# de0-nano_RMII.net
KiCad netlist of a schematic drawn in EAGLE
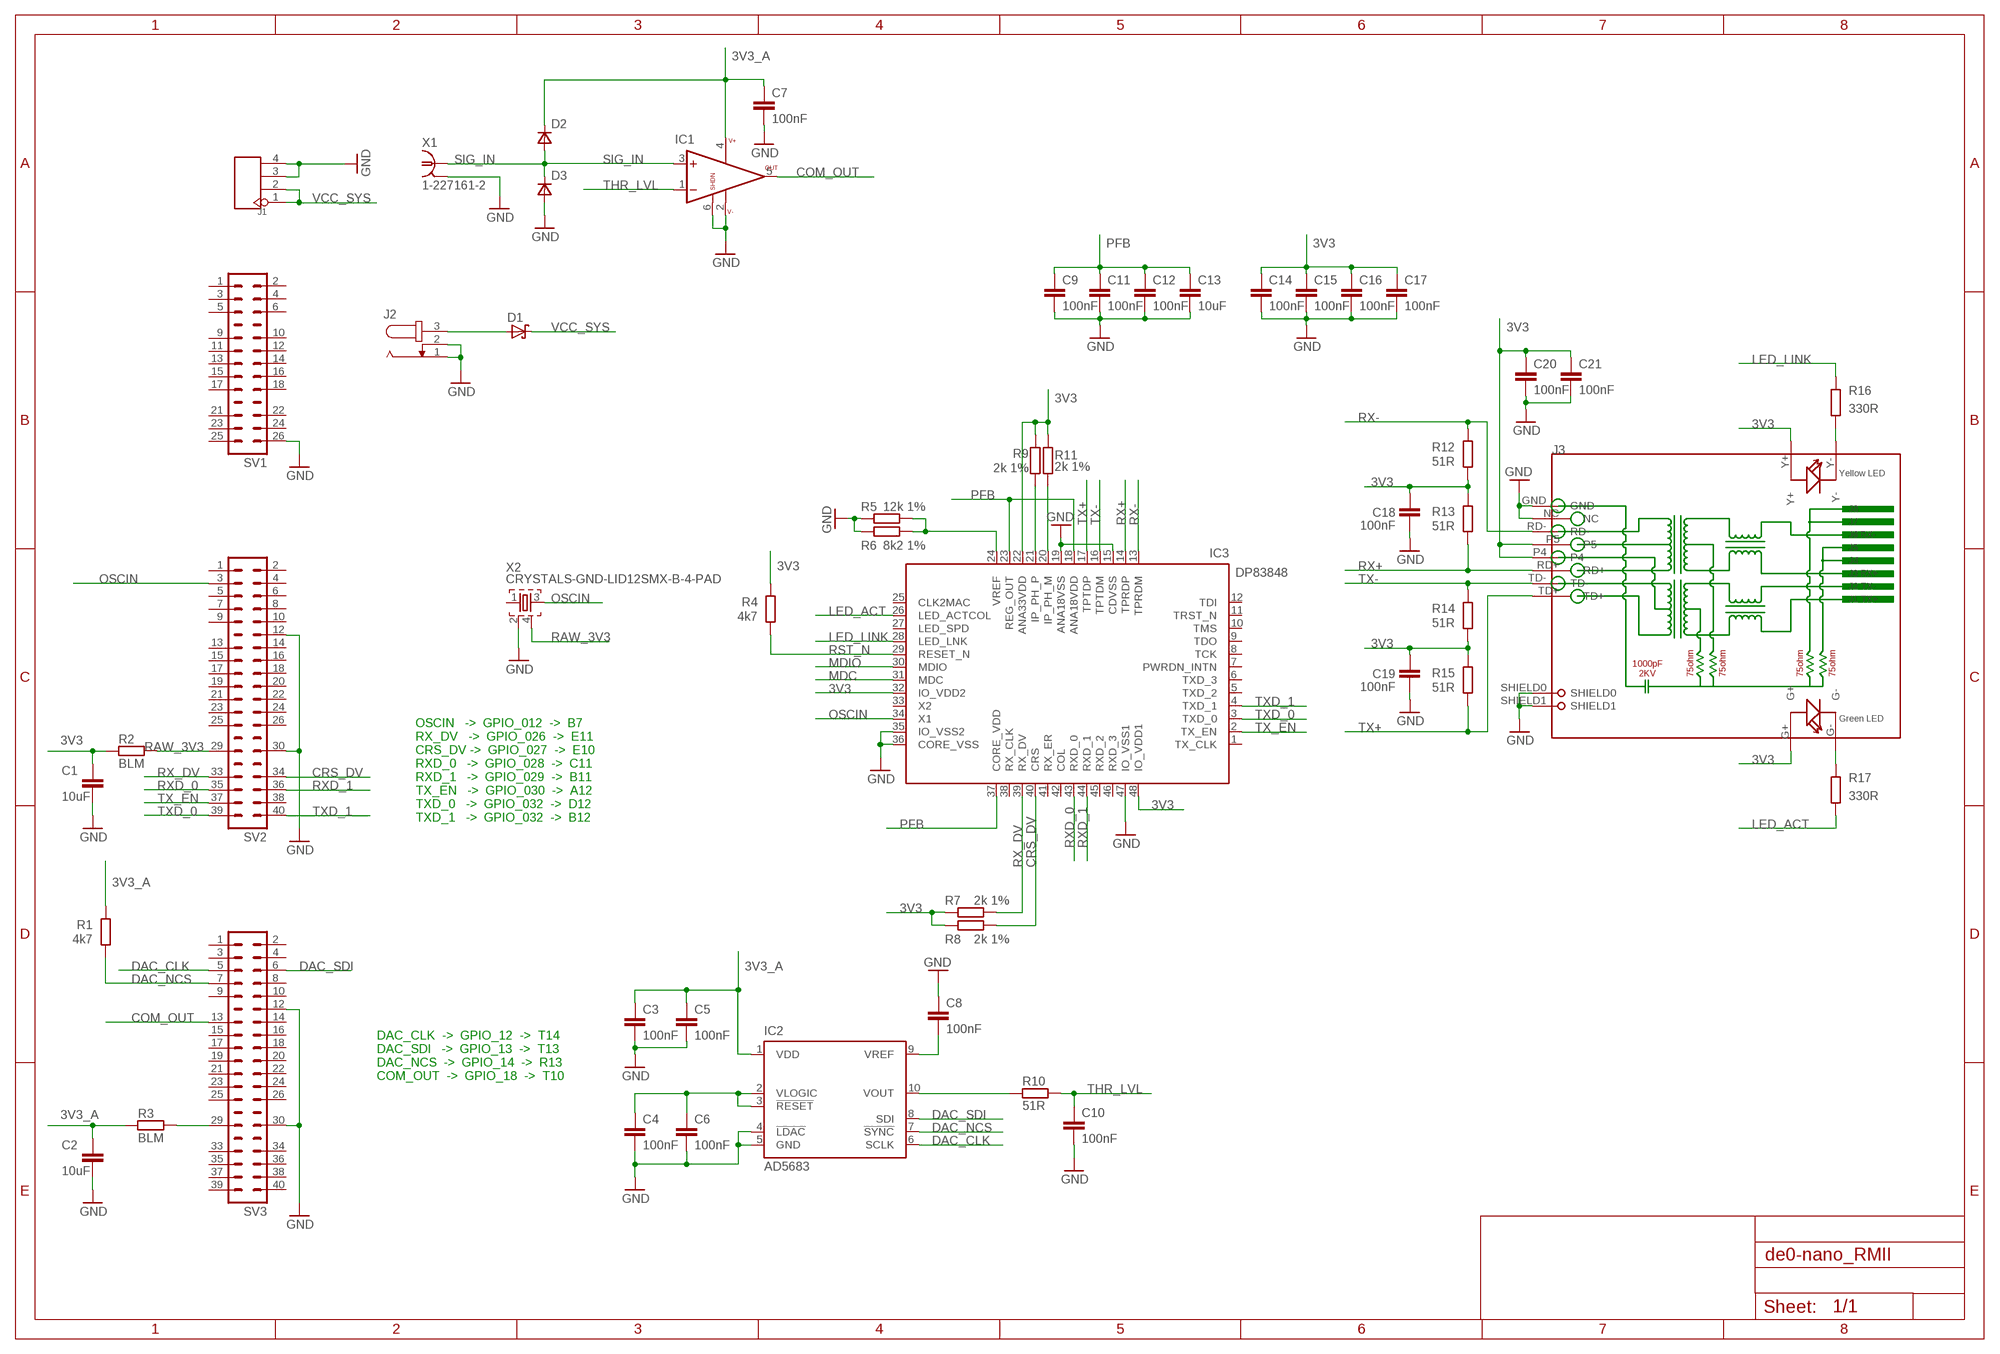
[diagram p0: schematic, sheet 1]

(export (version "E")
  (design (tool "Eeschema 10.0.6"))
  (components
    (comp (ref "C1")
      (value "10uF")
      (footprint "eagle-import:C0805")
      (libsource (lib "eagle-import") (part "C-EUC0805"))
    )
    (comp (ref "C2")
      (value "10uF")
      (footprint "eagle-import:C0805")
      (libsource (lib "eagle-import") (part "C-EUC0805"))
    )
    (comp (ref "C3")
      (value "100nF")
      (footprint "eagle-import:C0603")
      (libsource (lib "eagle-import") (part "C-EUC0603"))
    )
    (comp (ref "C4")
      (value "100nF")
      (footprint "eagle-import:C0603")
      (libsource (lib "eagle-import") (part "C-EUC0603"))
    )
    (comp (ref "C5")
      (value "100nF")
      (footprint "eagle-import:C0603")
      (libsource (lib "eagle-import") (part "C-EUC0603"))
    )
    (comp (ref "C6")
      (value "100nF")
      (footprint "eagle-import:C0603")
      (libsource (lib "eagle-import") (part "C-EUC0603"))
    )
    (comp (ref "C7")
      (value "100nF")
      (footprint "eagle-import:C0603")
      (libsource (lib "eagle-import") (part "C-EUC0603"))
    )
    (comp (ref "C8")
      (value "100nF")
      (footprint "eagle-import:C0603")
      (libsource (lib "eagle-import") (part "C-EUC0603"))
    )
    (comp (ref "C9")
      (value "100nF")
      (footprint "eagle-import:C0603")
      (libsource (lib "eagle-import") (part "C-EUC0603"))
    )
    (comp (ref "C10")
      (value "100nF")
      (footprint "eagle-import:C0603")
      (libsource (lib "eagle-import") (part "C-EUC0603"))
    )
    (comp (ref "C11")
      (value "100nF")
      (footprint "eagle-import:C0603")
      (libsource (lib "eagle-import") (part "C-EUC0603"))
    )
    (comp (ref "C12")
      (value "100nF")
      (footprint "eagle-import:C0603")
      (libsource (lib "eagle-import") (part "C-EUC0603"))
    )
    (comp (ref "C13")
      (value "10uF")
      (footprint "eagle-import:C0805")
      (libsource (lib "eagle-import") (part "C-EUC0805"))
    )
    (comp (ref "C14")
      (value "100nF")
      (footprint "eagle-import:C0603")
      (libsource (lib "eagle-import") (part "C-EUC0603"))
    )
    (comp (ref "C15")
      (value "100nF")
      (footprint "eagle-import:C0603")
      (libsource (lib "eagle-import") (part "C-EUC0603"))
    )
    (comp (ref "C16")
      (value "100nF")
      (footprint "eagle-import:C0603")
      (libsource (lib "eagle-import") (part "C-EUC0603"))
    )
    (comp (ref "C17")
      (value "100nF")
      (footprint "eagle-import:C0603")
      (libsource (lib "eagle-import") (part "C-EUC0603"))
    )
    (comp (ref "C18")
      (value "100nF")
      (footprint "eagle-import:C0603")
      (libsource (lib "eagle-import") (part "C-EUC0603"))
    )
    (comp (ref "C19")
      (value "100nF")
      (footprint "eagle-import:C0603")
      (libsource (lib "eagle-import") (part "C-EUC0603"))
    )
    (comp (ref "C20")
      (value "100nF")
      (footprint "eagle-import:C0603")
      (libsource (lib "eagle-import") (part "C-EUC0603"))
    )
    (comp (ref "C21")
      (value "100nF")
      (footprint "eagle-import:C0603")
      (libsource (lib "eagle-import") (part "C-EUC0603"))
    )
    (comp (ref "D1")
      (value "SCHOTTKY-DIODESMC")
      (footprint "eagle-import:SMC")
      (libsource (lib "eagle-import") (part "SCHOTTKY-DIODESMC"))
    )
    (comp (ref "D2")
      (value "DSOD323")
      (footprint "eagle-import:SOD323")
      (fields (field (name "MPN") "CDSOD323-T05C"))
      (libsource (lib "eagle-import") (part "DSOD323"))
    )
    (comp (ref "D3")
      (value "DSOD323")
      (footprint "eagle-import:SOD323")
      (fields (field (name "MPN") "CDSOD323-T05C"))
      (libsource (lib "eagle-import") (part "DSOD323"))
    )
    (comp (ref "IC1")
      (value "LT1719")
      (footprint "eagle-import:TSOT23-6")
      (libsource (lib "eagle-import") (part "LT1719"))
    )
    (comp (ref "IC2")
      (value "AD5683")
      (footprint "eagle-import:SO10")
      (fields (field (name "MPN") "SSM2167Z-EVAL"))
      (libsource (lib "eagle-import") (part "AD5683"))
    )
    (comp (ref "IC3")
      (value "DP83848")
      (footprint "eagle-import:LQFP48")
      (fields (field (name "MPN") "DP83848VYB"))
      (libsource (lib "eagle-import") (part "DP83848"))
    )
    (comp (ref "J1")
      (value "HEADER-4P-60/35MIL")
      (footprint "eagle-import:4P-65_35MIL")
      (libsource (lib "eagle-import") (part "HEADER-4P-60/35MIL"))
    )
    (comp (ref "J2")
      (value "JACK-PLUG1")
      (footprint "eagle-import:SPC4078")
      (libsource (lib "eagle-import") (part "JACK-PLUG1"))
    )
    (comp (ref "J3")
      (value "RJ45-HR911105A-HR911105A")
      (footprint "eagle-import:RJ45")
      (libsource (lib "eagle-import") (part "RJ45-HR911105A-HR911105A"))
    )
    (comp (ref "R1")
      (value "4k7")
      (footprint "eagle-import:R0603")
      (libsource (lib "eagle-import") (part "R-EU_R0603"))
    )
    (comp (ref "R2")
      (value "BLM")
      (footprint "eagle-import:R0603")
      (libsource (lib "eagle-import") (part "R-EU_R0603"))
    )
    (comp (ref "R3")
      (value "BLM")
      (footprint "eagle-import:R0603")
      (libsource (lib "eagle-import") (part "R-EU_R0603"))
    )
    (comp (ref "R4")
      (value "4k7")
      (footprint "eagle-import:R0603")
      (libsource (lib "eagle-import") (part "R-EU_R0603"))
    )
    (comp (ref "R5")
      (value "12k 1%")
      (footprint "eagle-import:R0603")
      (libsource (lib "eagle-import") (part "R-EU_R0603"))
    )
    (comp (ref "R6")
      (value "8k2 1%")
      (footprint "eagle-import:R0603")
      (libsource (lib "eagle-import") (part "R-EU_R0603"))
    )
    (comp (ref "R7")
      (value "2k 1%")
      (footprint "eagle-import:R0603")
      (libsource (lib "eagle-import") (part "R-EU_R0603"))
    )
    (comp (ref "R8")
      (value "2k 1%")
      (footprint "eagle-import:R0603")
      (libsource (lib "eagle-import") (part "R-EU_R0603"))
    )
    (comp (ref "R9")
      (value "2k 1%")
      (footprint "eagle-import:R0603")
      (libsource (lib "eagle-import") (part "R-EU_R0603"))
    )
    (comp (ref "R10")
      (value "51R")
      (footprint "eagle-import:R0603")
      (libsource (lib "eagle-import") (part "R-EU_R0603"))
    )
    (comp (ref "R11")
      (value "2k 1%")
      (footprint "eagle-import:R0603")
      (libsource (lib "eagle-import") (part "R-EU_R0603"))
    )
    (comp (ref "R12")
      (value "51R")
      (footprint "eagle-import:R0603")
      (libsource (lib "eagle-import") (part "R-EU_R0603"))
    )
    (comp (ref "R13")
      (value "51R")
      (footprint "eagle-import:R0603")
      (libsource (lib "eagle-import") (part "R-EU_R0603"))
    )
    (comp (ref "R14")
      (value "51R")
      (footprint "eagle-import:R0603")
      (libsource (lib "eagle-import") (part "R-EU_R0603"))
    )
    (comp (ref "R15")
      (value "51R")
      (footprint "eagle-import:R0603")
      (libsource (lib "eagle-import") (part "R-EU_R0603"))
    )
    (comp (ref "R16")
      (value "330R")
      (footprint "eagle-import:R0603")
      (libsource (lib "eagle-import") (part "R-EU_R0603"))
    )
    (comp (ref "R17")
      (value "330R")
      (footprint "eagle-import:R0603")
      (libsource (lib "eagle-import") (part "R-EU_R0603"))
    )
    (comp (ref "SV1")
      (value "MA13-2_ALT")
      (footprint "eagle-import:MA13-2_ALT")
      (libsource (lib "eagle-import") (part "MA13-2_ALT"))
    )
    (comp (ref "SV2")
      (value "MA20-2_ALT")
      (footprint "eagle-import:MA20-2_ALT")
      (libsource (lib "eagle-import") (part "MA20-2_ALT"))
    )
    (comp (ref "SV3")
      (value "MA20-2_ALT")
      (footprint "eagle-import:MA20-2_ALT")
      (libsource (lib "eagle-import") (part "MA20-2_ALT"))
    )
    (comp (ref "X1")
      (value "1-227161-2")
      (footprint "eagle-import:AMP_227161")
      (libsource (lib "eagle-import") (part "?2271611--2"))
    )
    (comp (ref "X2")
      (value "CRYSTALS-GND-LID12SMX-B-4-PAD")
      (footprint "eagle-import:7.5X5-4-PAD")
      (libsource (lib "eagle-import") (part "CRYSTALS-GND-LID-4-PAD12SMX-B"))
    )
  )
  (nets
    (net (code "1") (name "/3V3") (class "Default")
      (node (ref "C1") (pin "1") (pinfunction "1_1") (pintype "passive"))
      (node (ref "C14") (pin "1") (pinfunction "1_1") (pintype "passive"))
      (node (ref "C15") (pin "1") (pinfunction "1_1") (pintype "passive"))
      (node (ref "C16") (pin "1") (pinfunction "1_1") (pintype "passive"))
      (node (ref "C17") (pin "1") (pinfunction "1_1") (pintype "passive"))
      (node (ref "C18") (pin "1") (pinfunction "1_1") (pintype "passive"))
      (node (ref "C19") (pin "1") (pinfunction "1_1") (pintype "passive"))
      (node (ref "C20") (pin "1") (pinfunction "1_1") (pintype "passive"))
      (node (ref "C21") (pin "1") (pinfunction "1_1") (pintype "passive"))
      (node (ref "IC3") (pin "22") (pinfunction "ANA33VDD_22") (pintype "power_in"))
      (node (ref "IC3") (pin "32") (pinfunction "IO_VDD2_32") (pintype "power_in"))
      (node (ref "IC3") (pin "48") (pinfunction "IO_VDD1_48") (pintype "power_in"))
      (node (ref "J3") (pin "G+") (pinfunction "G+_G+") (pintype "bidirectional"))
      (node (ref "J3") (pin "P4") (pinfunction "P4_P4") (pintype "bidirectional"))
      (node (ref "J3") (pin "P5") (pinfunction "P5_P5") (pintype "bidirectional"))
      (node (ref "J3") (pin "Y+") (pinfunction "Y+_Y+") (pintype "bidirectional"))
      (node (ref "R11") (pin "2") (pinfunction "2_2") (pintype "passive"))
      (node (ref "R12") (pin "2") (pinfunction "2_2") (pintype "passive"))
      (node (ref "R13") (pin "1") (pinfunction "1_1") (pintype "passive"))
      (node (ref "R14") (pin "2") (pinfunction "2_2") (pintype "passive"))
      (node (ref "R15") (pin "1") (pinfunction "1_1") (pintype "passive"))
      (node (ref "R2") (pin "1") (pinfunction "1_1") (pintype "passive"))
      (node (ref "R4") (pin "1") (pinfunction "1_1") (pintype "passive"))
      (node (ref "R7") (pin "2") (pinfunction "2_2") (pintype "passive"))
      (node (ref "R8") (pin "2") (pinfunction "2_2") (pintype "passive"))
      (node (ref "R9") (pin "2") (pinfunction "2_2") (pintype "passive"))
    )
    (net (code "2") (name "/3V3_A") (class "Default")
      (node (ref "C2") (pin "1") (pinfunction "1_1") (pintype "passive"))
      (node (ref "C3") (pin "1") (pinfunction "1_1") (pintype "passive"))
      (node (ref "C5") (pin "1") (pinfunction "1_1") (pintype "passive"))
      (node (ref "C7") (pin "1") (pinfunction "1_1") (pintype "passive"))
      (node (ref "D2") (pin "1") (pinfunction "C_1") (pintype "passive"))
      (node (ref "IC1") (pin "4") (pinfunction "V+_4") (pintype "power_in"))
      (node (ref "IC2") (pin "1") (pinfunction "VDD_1") (pintype "power_in"))
      (node (ref "R1") (pin "1") (pinfunction "1_1") (pintype "passive"))
      (node (ref "R3") (pin "1") (pinfunction "1_1") (pintype "passive"))
    )
    (net (code "3") (name "/COM_OUT") (class "Default")
      (node (ref "IC1") (pin "5") (pinfunction "OUT_5") (pintype "output"))
      (node (ref "SV3") (pin "13") (pinfunction "13_13") (pintype "passive"))
    )
    (net (code "4") (name "/CRS_DV") (class "Default")
      (node (ref "IC3") (pin "40") (pinfunction "CRS_40") (pintype "bidirectional"))
      (node (ref "R8") (pin "1") (pinfunction "1_1") (pintype "passive"))
      (node (ref "SV2") (pin "34") (pinfunction "34_34") (pintype "passive"))
    )
    (net (code "5") (name "/DAC_CLK") (class "Default")
      (node (ref "IC2") (pin "6") (pinfunction "SCLK_6") (pintype "passive"))
      (node (ref "SV3") (pin "5") (pinfunction "5_5") (pintype "passive"))
    )
    (net (code "6") (name "/DAC_NCS") (class "Default")
      (node (ref "IC2") (pin "7") (pinfunction "~{SYNC}_7") (pintype "passive"))
      (node (ref "R1") (pin "2") (pinfunction "2_2") (pintype "passive"))
      (node (ref "SV3") (pin "7") (pinfunction "7_7") (pintype "passive"))
    )
    (net (code "7") (name "/DAC_SDI") (class "Default")
      (node (ref "IC2") (pin "8") (pinfunction "SDI_8") (pintype "passive"))
      (node (ref "SV3") (pin "6") (pinfunction "6_6") (pintype "passive"))
    )
    (net (code "8") (name "/LED_ACT") (class "Default")
      (node (ref "IC3") (pin "26") (pinfunction "LED_ACTCOL_26") (pintype "bidirectional"))
      (node (ref "R17") (pin "1") (pinfunction "1_1") (pintype "passive"))
    )
    (net (code "9") (name "/LED_LINK") (class "Default")
      (node (ref "IC3") (pin "28") (pinfunction "LED_LNK_28") (pintype "bidirectional"))
      (node (ref "R16") (pin "2") (pinfunction "2_2") (pintype "passive"))
    )
    (net (code "10") (name "/MDC") (class "Default")
      (node (ref "IC3") (pin "31") (pinfunction "MDC_31") (pintype "input"))
    )
    (net (code "11") (name "/MDIO") (class "Default")
      (node (ref "IC3") (pin "30") (pinfunction "MDIO_30") (pintype "bidirectional"))
    )
    (net (code "12") (name "/OSCIN") (class "Default")
      (node (ref "IC3") (pin "34") (pinfunction "X1_34") (pintype "input"))
      (node (ref "SV2") (pin "3") (pinfunction "3_3") (pintype "passive"))
      (node (ref "X2") (pin "3") (pinfunction "3_3") (pintype "passive"))
    )
    (net (code "13") (name "/PFB") (class "Default")
      (node (ref "C11") (pin "1") (pinfunction "1_1") (pintype "passive"))
      (node (ref "C12") (pin "1") (pinfunction "1_1") (pintype "passive"))
      (node (ref "C13") (pin "1") (pinfunction "1_1") (pintype "passive"))
      (node (ref "C9") (pin "1") (pinfunction "1_1") (pintype "passive"))
      (node (ref "IC3") (pin "18") (pinfunction "ANA18VDD_18") (pintype "power_in"))
      (node (ref "IC3") (pin "23") (pinfunction "REG_OUT_23") (pintype "output"))
      (node (ref "IC3") (pin "37") (pinfunction "CORE_VDD_37") (pintype "power_in"))
    )
    (net (code "14") (name "/RAW_3V3") (class "Default")
      (node (ref "R2") (pin "2") (pinfunction "2_2") (pintype "passive"))
      (node (ref "SV2") (pin "29") (pinfunction "29_29") (pintype "passive"))
      (node (ref "X2") (pin "4") (pinfunction "4_4") (pintype "passive"))
    )
    (net (code "15") (name "/RST_N") (class "Default")
      (node (ref "IC3") (pin "29") (pinfunction "RESET_N_29") (pintype "input"))
      (node (ref "R4") (pin "2") (pinfunction "2_2") (pintype "passive"))
    )
    (net (code "16") (name "/RX+") (class "Default")
      (node (ref "IC3") (pin "14") (pinfunction "TPRDP_14") (pintype "bidirectional"))
      (node (ref "J3") (pin "RD+") (pinfunction "RD+_RD+") (pintype "bidirectional"))
      (node (ref "R13") (pin "2") (pinfunction "2_2") (pintype "passive"))
    )
    (net (code "17") (name "/RX-") (class "Default")
      (node (ref "IC3") (pin "13") (pinfunction "TPRDM_13") (pintype "bidirectional"))
      (node (ref "J3") (pin "RD-") (pinfunction "RD-_RD-") (pintype "bidirectional"))
      (node (ref "R12") (pin "1") (pinfunction "1_1") (pintype "passive"))
    )
    (net (code "18") (name "/RXD_0") (class "Default")
      (node (ref "IC3") (pin "43") (pinfunction "RXD_0_43") (pintype "bidirectional"))
      (node (ref "SV2") (pin "35") (pinfunction "35_35") (pintype "passive"))
    )
    (net (code "19") (name "/RXD_1") (class "Default")
      (node (ref "IC3") (pin "44") (pinfunction "RXD_1_44") (pintype "bidirectional"))
      (node (ref "SV2") (pin "36") (pinfunction "36_36") (pintype "passive"))
    )
    (net (code "20") (name "/RX_DV") (class "Default")
      (node (ref "IC3") (pin "39") (pinfunction "RX_DV_39") (pintype "bidirectional"))
      (node (ref "R7") (pin "1") (pinfunction "1_1") (pintype "passive"))
      (node (ref "SV2") (pin "33") (pinfunction "33_33") (pintype "passive"))
    )
    (net (code "21") (name "/SIG_IN") (class "Default")
      (node (ref "D2") (pin "2") (pinfunction "A_2") (pintype "passive"))
      (node (ref "D3") (pin "1") (pinfunction "C_1") (pintype "passive"))
      (node (ref "IC1") (pin "3") (pinfunction "+IN_3") (pintype "input"))
      (node (ref "X1") (pin "1") (pinfunction "1_1") (pintype "passive"))
    )
    (net (code "22") (name "/THR_LVL") (class "Default")
      (node (ref "C10") (pin "1") (pinfunction "1_1") (pintype "passive"))
      (node (ref "IC1") (pin "1") (pinfunction "-IN_1") (pintype "input"))
      (node (ref "R10") (pin "2") (pinfunction "2_2") (pintype "passive"))
    )
    (net (code "23") (name "/TX+") (class "Default")
      (node (ref "IC3") (pin "17") (pinfunction "TPTDP_17") (pintype "bidirectional"))
      (node (ref "J3") (pin "TD+") (pinfunction "TD+_TD+") (pintype "bidirectional"))
      (node (ref "R15") (pin "2") (pinfunction "2_2") (pintype "passive"))
    )
    (net (code "24") (name "/TX-") (class "Default")
      (node (ref "IC3") (pin "16") (pinfunction "TPTDM_16") (pintype "bidirectional"))
      (node (ref "J3") (pin "TD-") (pinfunction "TD-_TD-") (pintype "bidirectional"))
      (node (ref "R14") (pin "1") (pinfunction "1_1") (pintype "passive"))
    )
    (net (code "25") (name "/TXD_0") (class "Default")
      (node (ref "IC3") (pin "3") (pinfunction "TXD_0_3") (pintype "bidirectional"))
      (node (ref "SV2") (pin "39") (pinfunction "39_39") (pintype "passive"))
    )
    (net (code "26") (name "/TXD_1") (class "Default")
      (node (ref "IC3") (pin "4") (pinfunction "TXD_1_4") (pintype "bidirectional"))
      (node (ref "SV2") (pin "40") (pinfunction "40_40") (pintype "passive"))
    )
    (net (code "27") (name "/TX_EN") (class "Default")
      (node (ref "IC3") (pin "2") (pinfunction "TX_EN_2") (pintype "bidirectional"))
      (node (ref "SV2") (pin "37") (pinfunction "37_37") (pintype "passive"))
    )
    (net (code "28") (name "/VCC_SYS") (class "Default")
      (node (ref "D1") (pin "C") (pinfunction "C_C") (pintype "passive"))
      (node (ref "J1") (pin "1") (pinfunction "P$1_1") (pintype "bidirectional"))
      (node (ref "J1") (pin "2") (pinfunction "P$2_2") (pintype "bidirectional"))
    )
    (net (code "29") (name "GND") (class "Default")
      (node (ref "C1") (pin "2") (pinfunction "2_2") (pintype "passive"))
      (node (ref "C10") (pin "2") (pinfunction "2_2") (pintype "passive"))
      (node (ref "C11") (pin "2") (pinfunction "2_2") (pintype "passive"))
      (node (ref "C12") (pin "2") (pinfunction "2_2") (pintype "passive"))
      (node (ref "C13") (pin "2") (pinfunction "2_2") (pintype "passive"))
      (node (ref "C14") (pin "2") (pinfunction "2_2") (pintype "passive"))
      (node (ref "C15") (pin "2") (pinfunction "2_2") (pintype "passive"))
      (node (ref "C16") (pin "2") (pinfunction "2_2") (pintype "passive"))
      (node (ref "C17") (pin "2") (pinfunction "2_2") (pintype "passive"))
      (node (ref "C18") (pin "2") (pinfunction "2_2") (pintype "passive"))
      (node (ref "C19") (pin "2") (pinfunction "2_2") (pintype "passive"))
      (node (ref "C2") (pin "2") (pinfunction "2_2") (pintype "passive"))
      (node (ref "C20") (pin "2") (pinfunction "2_2") (pintype "passive"))
      (node (ref "C21") (pin "2") (pinfunction "2_2") (pintype "passive"))
      (node (ref "C3") (pin "2") (pinfunction "2_2") (pintype "passive"))
      (node (ref "C4") (pin "2") (pinfunction "2_2") (pintype "passive"))
      (node (ref "C5") (pin "2") (pinfunction "2_2") (pintype "passive"))
      (node (ref "C6") (pin "2") (pinfunction "2_2") (pintype "passive"))
      (node (ref "C7") (pin "2") (pinfunction "2_2") (pintype "passive"))
      (node (ref "C8") (pin "2") (pinfunction "2_2") (pintype "passive"))
      (node (ref "C9") (pin "2") (pinfunction "2_2") (pintype "passive"))
      (node (ref "D3") (pin "2") (pinfunction "A_2") (pintype "passive"))
      (node (ref "IC1") (pin "2") (pinfunction "V-_2") (pintype "power_in"))
      (node (ref "IC1") (pin "6") (pinfunction "SHDN_6") (pintype "input"))
      (node (ref "IC2") (pin "4") (pinfunction "~{LDAC}_4") (pintype "output"))
      (node (ref "IC2") (pin "5") (pinfunction "GND_5") (pintype "power_in"))
      (node (ref "IC3") (pin "15") (pinfunction "CDVSS_15") (pintype "power_in"))
      (node (ref "IC3") (pin "19") (pinfunction "ANA18VSS_19") (pintype "power_in"))
      (node (ref "IC3") (pin "35") (pinfunction "IO_VSS2_35") (pintype "power_in"))
      (node (ref "IC3") (pin "36") (pinfunction "CORE_VSS_36") (pintype "power_in"))
      (node (ref "IC3") (pin "47") (pinfunction "IO_VSS1_47") (pintype "power_in"))
      (node (ref "J1") (pin "3") (pinfunction "P$3_3") (pintype "bidirectional"))
      (node (ref "J1") (pin "4") (pinfunction "P$4_4") (pintype "bidirectional"))
      (node (ref "J2") (pin "1") (pinfunction "1_1") (pintype "passive"))
      (node (ref "J2") (pin "2") (pinfunction "2_2") (pintype "passive"))
      (node (ref "J3") (pin "GND") (pinfunction "GND_GND") (pintype "bidirectional"))
      (node (ref "J3") (pin "NC") (pinfunction "NC_NC") (pintype "bidirectional"))
      (node (ref "J3") (pin "SHIELD0") (pinfunction "SHIELD0_SHIELD0") (pintype "bidirectional"))
      (node (ref "J3") (pin "SHIELD1") (pinfunction "SHIELD1_SHIELD1") (pintype "bidirectional"))
      (node (ref "R5") (pin "2") (pinfunction "2_2") (pintype "passive"))
      (node (ref "R6") (pin "2") (pinfunction "2_2") (pintype "passive"))
      (node (ref "SV1") (pin "26") (pinfunction "26_26") (pintype "passive"))
      (node (ref "SV2") (pin "12") (pinfunction "12_12") (pintype "passive"))
      (node (ref "SV2") (pin "30") (pinfunction "30_30") (pintype "passive"))
      (node (ref "SV3") (pin "12") (pinfunction "12_12") (pintype "passive"))
      (node (ref "SV3") (pin "30") (pinfunction "30_30") (pintype "passive"))
      (node (ref "X1") (pin "2") (pinfunction "2_2") (pintype "passive"))
      (node (ref "X2") (pin "2") (pinfunction "2_2") (pintype "passive"))
    )
    (net (code "30") (name "Net-(D1-PadA)") (class "Default")
      (node (ref "D1") (pin "A") (pinfunction "A_A") (pintype "passive"))
      (node (ref "J2") (pin "3") (pinfunction "3_3") (pintype "passive"))
    )
    (net (code "31") (name "Net-(IC2-VLOGIC)") (class "Default")
      (node (ref "C4") (pin "1") (pinfunction "1_1") (pintype "passive"))
      (node (ref "C6") (pin "1") (pinfunction "1_1") (pintype "passive"))
      (node (ref "IC2") (pin "2") (pinfunction "VLOGIC_2") (pintype "bidirectional"))
      (node (ref "IC2") (pin "3") (pinfunction "~{RESET}_3") (pintype "bidirectional"))
    )
    (net (code "32") (name "Net-(IC2-VOUT)") (class "Default")
      (node (ref "IC2") (pin "10") (pinfunction "VOUT_10") (pintype "output"))
      (node (ref "R10") (pin "1") (pinfunction "1_1") (pintype "passive"))
    )
    (net (code "33") (name "Net-(IC2-VREF)") (class "Default")
      (node (ref "C8") (pin "1") (pinfunction "1_1") (pintype "passive"))
      (node (ref "IC2") (pin "9") (pinfunction "VREF_9") (pintype "input"))
    )
    (net (code "34") (name "Net-(IC3-IP_PH_M)") (class "Default")
      (node (ref "IC3") (pin "20") (pinfunction "IP_PH_M_20") (pintype "input"))
      (node (ref "R11") (pin "1") (pinfunction "1_1") (pintype "passive"))
    )
    (net (code "35") (name "Net-(IC3-IP_PH_P)") (class "Default")
      (node (ref "IC3") (pin "21") (pinfunction "IP_PH_P_21") (pintype "input"))
      (node (ref "R9") (pin "1") (pinfunction "1_1") (pintype "passive"))
    )
    (net (code "36") (name "Net-(IC3-VREF)") (class "Default")
      (node (ref "IC3") (pin "24") (pinfunction "VREF_24") (pintype "bidirectional"))
      (node (ref "R5") (pin "1") (pinfunction "1_1") (pintype "passive"))
      (node (ref "R6") (pin "1") (pinfunction "1_1") (pintype "passive"))
    )
    (net (code "37") (name "Net-(J3-PadG-)") (class "Default")
      (node (ref "J3") (pin "G-") (pinfunction "G-_G-") (pintype "bidirectional"))
      (node (ref "R17") (pin "2") (pinfunction "2_2") (pintype "passive"))
    )
    (net (code "38") (name "Net-(J3-PadY-)") (class "Default")
      (node (ref "J3") (pin "Y-") (pinfunction "Y-_Y-") (pintype "bidirectional"))
      (node (ref "R16") (pin "1") (pinfunction "1_1") (pintype "passive"))
    )
    (net (code "39") (name "Net-(R3-Pad2)") (class "Default")
      (node (ref "R3") (pin "2") (pinfunction "2_2") (pintype "passive"))
      (node (ref "SV3") (pin "29") (pinfunction "29_29") (pintype "passive"))
    )
    (net (code "40") (name "unconnected-(IC3-CLK2MAC-Pad25)") (class "Default")
      (node (ref "IC3") (pin "25") (pinfunction "CLK2MAC_25") (pintype "bidirectional"))
    )
    (net (code "41") (name "unconnected-(IC3-COL-Pad42)") (class "Default")
      (node (ref "IC3") (pin "42") (pinfunction "COL_42") (pintype "bidirectional"))
    )
    (net (code "42") (name "unconnected-(IC3-LED_SPD-Pad27)") (class "Default")
      (node (ref "IC3") (pin "27") (pinfunction "LED_SPD_27") (pintype "bidirectional"))
    )
    (net (code "43") (name "unconnected-(IC3-PWRDN_INTN-Pad7)") (class "Default")
      (node (ref "IC3") (pin "7") (pinfunction "PWRDN_INTN_7") (pintype "bidirectional"))
    )
    (net (code "44") (name "unconnected-(IC3-RXD_2-Pad45)") (class "Default")
      (node (ref "IC3") (pin "45") (pinfunction "RXD_2_45") (pintype "bidirectional"))
    )
    (net (code "45") (name "unconnected-(IC3-RXD_3-Pad46)") (class "Default")
      (node (ref "IC3") (pin "46") (pinfunction "RXD_3_46") (pintype "bidirectional"))
    )
    (net (code "46") (name "unconnected-(IC3-RX_CLK-Pad38)") (class "Default")
      (node (ref "IC3") (pin "38") (pinfunction "RX_CLK_38") (pintype "bidirectional"))
    )
    (net (code "47") (name "unconnected-(IC3-RX_ER-Pad41)") (class "Default")
      (node (ref "IC3") (pin "41") (pinfunction "RX_ER_41") (pintype "bidirectional"))
    )
    (net (code "48") (name "unconnected-(IC3-TCK-Pad8)") (class "Default")
      (node (ref "IC3") (pin "8") (pinfunction "TCK_8") (pintype "input"))
    )
    (net (code "49") (name "unconnected-(IC3-TDI-Pad12)") (class "Default")
      (node (ref "IC3") (pin "12") (pinfunction "TDI_12") (pintype "input"))
    )
    (net (code "50") (name "unconnected-(IC3-TDO-Pad9)") (class "Default")
      (node (ref "IC3") (pin "9") (pinfunction "TDO_9") (pintype "output"))
    )
    (net (code "51") (name "unconnected-(IC3-TMS-Pad10)") (class "Default")
      (node (ref "IC3") (pin "10") (pinfunction "TMS_10") (pintype "input"))
    )
    (net (code "52") (name "unconnected-(IC3-TRST_N-Pad11)") (class "Default")
      (node (ref "IC3") (pin "11") (pinfunction "TRST_N_11") (pintype "input"))
    )
    (net (code "53") (name "unconnected-(IC3-TXD_2-Pad5)") (class "Default")
      (node (ref "IC3") (pin "5") (pinfunction "TXD_2_5") (pintype "bidirectional"))
    )
    (net (code "54") (name "unconnected-(IC3-TXD_3-Pad6)") (class "Default")
      (node (ref "IC3") (pin "6") (pinfunction "TXD_3_6") (pintype "bidirectional"))
    )
    (net (code "55") (name "unconnected-(IC3-TX_CLK-Pad1)") (class "Default")
      (node (ref "IC3") (pin "1") (pinfunction "TX_CLK_1") (pintype "bidirectional"))
    )
    (net (code "56") (name "unconnected-(IC3-X2-Pad33)") (class "Default")
      (node (ref "IC3") (pin "33") (pinfunction "X2_33") (pintype "output"))
    )
    (net (code "57") (name "unconnected-(SV1-Pad1)") (class "Default")
      (node (ref "SV1") (pin "1") (pinfunction "1_1") (pintype "passive"))
    )
    (net (code "58") (name "unconnected-(SV1-Pad2)") (class "Default")
      (node (ref "SV1") (pin "2") (pinfunction "2_2") (pintype "passive"))
    )
    (net (code "59") (name "unconnected-(SV1-Pad3)") (class "Default")
      (node (ref "SV1") (pin "3") (pinfunction "3_3") (pintype "passive"))
    )
    (net (code "60") (name "unconnected-(SV1-Pad4)") (class "Default")
      (node (ref "SV1") (pin "4") (pinfunction "4_4") (pintype "passive"))
    )
    (net (code "61") (name "unconnected-(SV1-Pad5)") (class "Default")
      (node (ref "SV1") (pin "5") (pinfunction "5_5") (pintype "passive"))
    )
    (net (code "62") (name "unconnected-(SV1-Pad6)") (class "Default")
      (node (ref "SV1") (pin "6") (pinfunction "6_6") (pintype "passive"))
    )
    (net (code "63") (name "unconnected-(SV1-Pad9)") (class "Default")
      (node (ref "SV1") (pin "9") (pinfunction "9_9") (pintype "passive"))
    )
    (net (code "64") (name "unconnected-(SV1-Pad10)") (class "Default")
      (node (ref "SV1") (pin "10") (pinfunction "10_10") (pintype "passive"))
    )
    (net (code "65") (name "unconnected-(SV1-Pad11)") (class "Default")
      (node (ref "SV1") (pin "11") (pinfunction "11_11") (pintype "passive"))
    )
    (net (code "66") (name "unconnected-(SV1-Pad12)") (class "Default")
      (node (ref "SV1") (pin "12") (pinfunction "12_12") (pintype "passive"))
    )
    (net (code "67") (name "unconnected-(SV1-Pad13)") (class "Default")
      (node (ref "SV1") (pin "13") (pinfunction "13_13") (pintype "passive"))
    )
    (net (code "68") (name "unconnected-(SV1-Pad14)") (class "Default")
      (node (ref "SV1") (pin "14") (pinfunction "14_14") (pintype "passive"))
    )
    (net (code "69") (name "unconnected-(SV1-Pad15)") (class "Default")
      (node (ref "SV1") (pin "15") (pinfunction "15_15") (pintype "passive"))
    )
    (net (code "70") (name "unconnected-(SV1-Pad16)") (class "Default")
      (node (ref "SV1") (pin "16") (pinfunction "16_16") (pintype "passive"))
    )
    (net (code "71") (name "unconnected-(SV1-Pad17)") (class "Default")
      (node (ref "SV1") (pin "17") (pinfunction "17_17") (pintype "passive"))
    )
    (net (code "72") (name "unconnected-(SV1-Pad18)") (class "Default")
      (node (ref "SV1") (pin "18") (pinfunction "18_18") (pintype "passive"))
    )
    (net (code "73") (name "unconnected-(SV1-Pad21)") (class "Default")
      (node (ref "SV1") (pin "21") (pinfunction "21_21") (pintype "passive"))
    )
    (net (code "74") (name "unconnected-(SV1-Pad22)") (class "Default")
      (node (ref "SV1") (pin "22") (pinfunction "22_22") (pintype "passive"))
    )
    (net (code "75") (name "unconnected-(SV1-Pad23)") (class "Default")
      (node (ref "SV1") (pin "23") (pinfunction "23_23") (pintype "passive"))
    )
    (net (code "76") (name "unconnected-(SV1-Pad24)") (class "Default")
      (node (ref "SV1") (pin "24") (pinfunction "24_24") (pintype "passive"))
    )
    (net (code "77") (name "unconnected-(SV1-Pad25)") (class "Default")
      (node (ref "SV1") (pin "25") (pinfunction "25_25") (pintype "passive"))
    )
    (net (code "78") (name "unconnected-(SV2-Pad1)") (class "Default")
      (node (ref "SV2") (pin "1") (pinfunction "1_1") (pintype "passive"))
    )
    (net (code "79") (name "unconnected-(SV2-Pad2)") (class "Default")
      (node (ref "SV2") (pin "2") (pinfunction "2_2") (pintype "passive"))
    )
    (net (code "80") (name "unconnected-(SV2-Pad4)") (class "Default")
      (node (ref "SV2") (pin "4") (pinfunction "4_4") (pintype "passive"))
    )
    (net (code "81") (name "unconnected-(SV2-Pad5)") (class "Default")
      (node (ref "SV2") (pin "5") (pinfunction "5_5") (pintype "passive"))
    )
    (net (code "82") (name "unconnected-(SV2-Pad6)") (class "Default")
      (node (ref "SV2") (pin "6") (pinfunction "6_6") (pintype "passive"))
    )
    (net (code "83") (name "unconnected-(SV2-Pad7)") (class "Default")
      (node (ref "SV2") (pin "7") (pinfunction "7_7") (pintype "passive"))
    )
    (net (code "84") (name "unconnected-(SV2-Pad8)") (class "Default")
      (node (ref "SV2") (pin "8") (pinfunction "8_8") (pintype "passive"))
    )
    (net (code "85") (name "unconnected-(SV2-Pad9)") (class "Default")
      (node (ref "SV2") (pin "9") (pinfunction "9_9") (pintype "passive"))
    )
    (net (code "86") (name "unconnected-(SV2-Pad10)") (class "Default")
      (node (ref "SV2") (pin "10") (pinfunction "10_10") (pintype "passive"))
    )
    (net (code "87") (name "unconnected-(SV2-Pad13)") (class "Default")
      (node (ref "SV2") (pin "13") (pinfunction "13_13") (pintype "passive"))
    )
    (net (code "88") (name "unconnected-(SV2-Pad14)") (class "Default")
      (node (ref "SV2") (pin "14") (pinfunction "14_14") (pintype "passive"))
    )
    (net (code "89") (name "unconnected-(SV2-Pad15)") (class "Default")
      (node (ref "SV2") (pin "15") (pinfunction "15_15") (pintype "passive"))
    )
    (net (code "90") (name "unconnected-(SV2-Pad16)") (class "Default")
      (node (ref "SV2") (pin "16") (pinfunction "16_16") (pintype "passive"))
    )
    (net (code "91") (name "unconnected-(SV2-Pad17)") (class "Default")
      (node (ref "SV2") (pin "17") (pinfunction "17_17") (pintype "passive"))
    )
    (net (code "92") (name "unconnected-(SV2-Pad18)") (class "Default")
      (node (ref "SV2") (pin "18") (pinfunction "18_18") (pintype "passive"))
    )
    (net (code "93") (name "unconnected-(SV2-Pad19)") (class "Default")
      (node (ref "SV2") (pin "19") (pinfunction "19_19") (pintype "passive"))
    )
    (net (code "94") (name "unconnected-(SV2-Pad20)") (class "Default")
      (node (ref "SV2") (pin "20") (pinfunction "20_20") (pintype "passive"))
    )
    (net (code "95") (name "unconnected-(SV2-Pad21)") (class "Default")
      (node (ref "SV2") (pin "21") (pinfunction "21_21") (pintype "passive"))
    )
    (net (code "96") (name "unconnected-(SV2-Pad22)") (class "Default")
      (node (ref "SV2") (pin "22") (pinfunction "22_22") (pintype "passive"))
    )
    (net (code "97") (name "unconnected-(SV2-Pad23)") (class "Default")
      (node (ref "SV2") (pin "23") (pinfunction "23_23") (pintype "passive"))
    )
    (net (code "98") (name "unconnected-(SV2-Pad24)") (class "Default")
      (node (ref "SV2") (pin "24") (pinfunction "24_24") (pintype "passive"))
    )
    (net (code "99") (name "unconnected-(SV2-Pad25)") (class "Default")
      (node (ref "SV2") (pin "25") (pinfunction "25_25") (pintype "passive"))
    )
    (net (code "100") (name "unconnected-(SV2-Pad26)") (class "Default")
      (node (ref "SV2") (pin "26") (pinfunction "26_26") (pintype "passive"))
    )
    (net (code "101") (name "unconnected-(SV2-Pad38)") (class "Default")
      (node (ref "SV2") (pin "38") (pinfunction "38_38") (pintype "passive"))
    )
    (net (code "102") (name "unconnected-(SV3-Pad1)") (class "Default")
      (node (ref "SV3") (pin "1") (pinfunction "1_1") (pintype "passive"))
    )
    (net (code "103") (name "unconnected-(SV3-Pad2)") (class "Default")
      (node (ref "SV3") (pin "2") (pinfunction "2_2") (pintype "passive"))
    )
    (net (code "104") (name "unconnected-(SV3-Pad3)") (class "Default")
      (node (ref "SV3") (pin "3") (pinfunction "3_3") (pintype "passive"))
    )
    (net (code "105") (name "unconnected-(SV3-Pad4)") (class "Default")
      (node (ref "SV3") (pin "4") (pinfunction "4_4") (pintype "passive"))
    )
    (net (code "106") (name "unconnected-(SV3-Pad8)") (class "Default")
      (node (ref "SV3") (pin "8") (pinfunction "8_8") (pintype "passive"))
    )
    (net (code "107") (name "unconnected-(SV3-Pad9)") (class "Default")
      (node (ref "SV3") (pin "9") (pinfunction "9_9") (pintype "passive"))
    )
    (net (code "108") (name "unconnected-(SV3-Pad10)") (class "Default")
      (node (ref "SV3") (pin "10") (pinfunction "10_10") (pintype "passive"))
    )
    (net (code "109") (name "unconnected-(SV3-Pad14)") (class "Default")
      (node (ref "SV3") (pin "14") (pinfunction "14_14") (pintype "passive"))
    )
    (net (code "110") (name "unconnected-(SV3-Pad15)") (class "Default")
      (node (ref "SV3") (pin "15") (pinfunction "15_15") (pintype "passive"))
    )
    (net (code "111") (name "unconnected-(SV3-Pad16)") (class "Default")
      (node (ref "SV3") (pin "16") (pinfunction "16_16") (pintype "passive"))
    )
    (net (code "112") (name "unconnected-(SV3-Pad17)") (class "Default")
      (node (ref "SV3") (pin "17") (pinfunction "17_17") (pintype "passive"))
    )
    (net (code "113") (name "unconnected-(SV3-Pad18)") (class "Default")
      (node (ref "SV3") (pin "18") (pinfunction "18_18") (pintype "passive"))
    )
    (net (code "114") (name "unconnected-(SV3-Pad19)") (class "Default")
      (node (ref "SV3") (pin "19") (pinfunction "19_19") (pintype "passive"))
    )
    (net (code "115") (name "unconnected-(SV3-Pad20)") (class "Default")
      (node (ref "SV3") (pin "20") (pinfunction "20_20") (pintype "passive"))
    )
    (net (code "116") (name "unconnected-(SV3-Pad21)") (class "Default")
      (node (ref "SV3") (pin "21") (pinfunction "21_21") (pintype "passive"))
    )
    (net (code "117") (name "unconnected-(SV3-Pad22)") (class "Default")
      (node (ref "SV3") (pin "22") (pinfunction "22_22") (pintype "passive"))
    )
    (net (code "118") (name "unconnected-(SV3-Pad23)") (class "Default")
      (node (ref "SV3") (pin "23") (pinfunction "23_23") (pintype "passive"))
    )
    (net (code "119") (name "unconnected-(SV3-Pad24)") (class "Default")
      (node (ref "SV3") (pin "24") (pinfunction "24_24") (pintype "passive"))
    )
    (net (code "120") (name "unconnected-(SV3-Pad25)") (class "Default")
      (node (ref "SV3") (pin "25") (pinfunction "25_25") (pintype "passive"))
    )
    (net (code "121") (name "unconnected-(SV3-Pad26)") (class "Default")
      (node (ref "SV3") (pin "26") (pinfunction "26_26") (pintype "passive"))
    )
    (net (code "122") (name "unconnected-(SV3-Pad33)") (class "Default")
      (node (ref "SV3") (pin "33") (pinfunction "33_33") (pintype "passive"))
    )
    (net (code "123") (name "unconnected-(SV3-Pad34)") (class "Default")
      (node (ref "SV3") (pin "34") (pinfunction "34_34") (pintype "passive"))
    )
    (net (code "124") (name "unconnected-(SV3-Pad35)") (class "Default")
      (node (ref "SV3") (pin "35") (pinfunction "35_35") (pintype "passive"))
    )
    (net (code "125") (name "unconnected-(SV3-Pad36)") (class "Default")
      (node (ref "SV3") (pin "36") (pinfunction "36_36") (pintype "passive"))
    )
    (net (code "126") (name "unconnected-(SV3-Pad37)") (class "Default")
      (node (ref "SV3") (pin "37") (pinfunction "37_37") (pintype "passive"))
    )
    (net (code "127") (name "unconnected-(SV3-Pad38)") (class "Default")
      (node (ref "SV3") (pin "38") (pinfunction "38_38") (pintype "passive"))
    )
    (net (code "128") (name "unconnected-(SV3-Pad39)") (class "Default")
      (node (ref "SV3") (pin "39") (pinfunction "39_39") (pintype "passive"))
    )
    (net (code "129") (name "unconnected-(SV3-Pad40)") (class "Default")
      (node (ref "SV3") (pin "40") (pinfunction "40_40") (pintype "passive"))
    )
    (net (code "130") (name "unconnected-(X2-Pad1)") (class "Default")
      (node (ref "X2") (pin "1") (pinfunction "1_1") (pintype "passive"))
    )
  )
)
